# 03_Connectors.net
KiCad netlist of a schematic drawn in Altium Designer
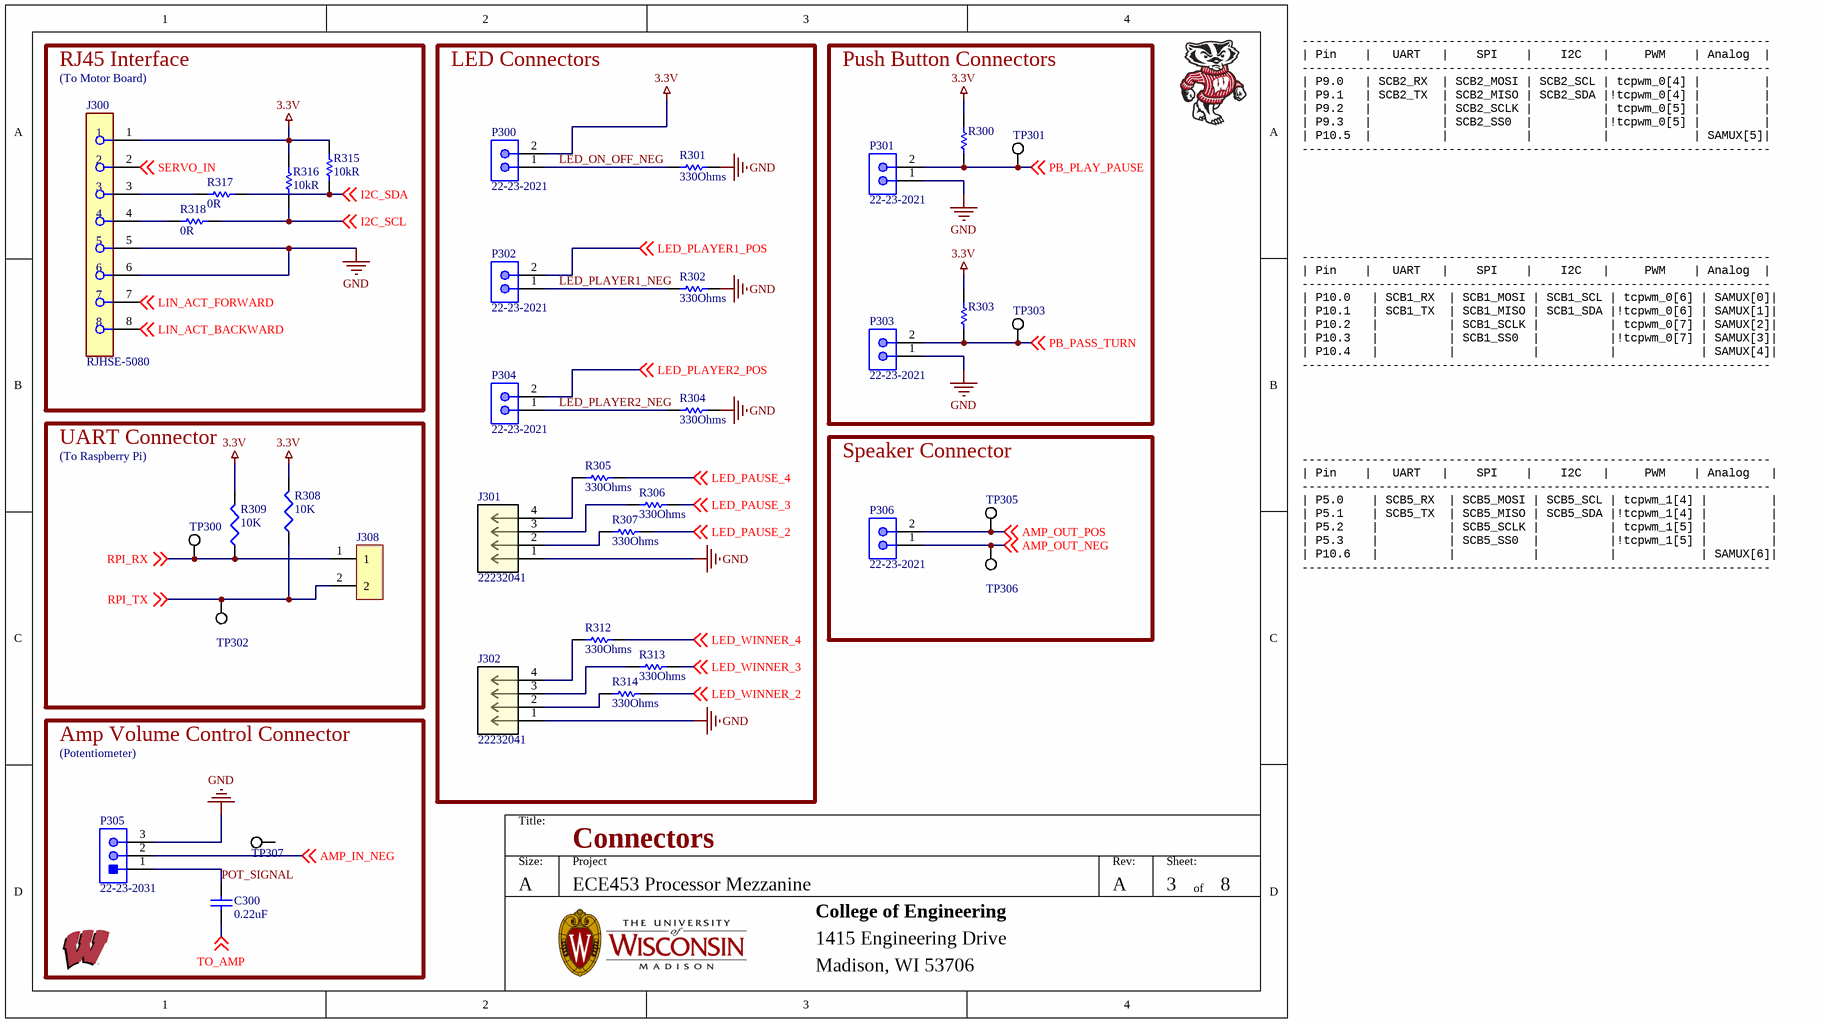
[diagram p0: 03_Connectors.SchDoc]

(export (version "E")
  (design (tool "Eeschema 10.0.6"))
  (components
    (comp (ref "C300")
      (value "0.22uF")
      (footprint "CAPC2012M")
      (description "Cap Ceramic 0.22uF 50V X7R 10% SMD 0805 125°C Plastic T/R")
      (fields
        (field (name "MANUFACTURER") "KEMET")
        (field (name "MANUFACTURER PART NUMBER") "C0805C224K5RACAUTO7210")
      )
      (libsource (lib "ECE453") (part "Cap_2"))
    )
    (comp (ref "J300")
      (value "RJHSE-5080")
      (footprint "FP-RJHSE-5080-MFG")
      (description "CONN MOD JACK 8P8C R/A UNSHLD")
      (fields
        (field (name "OCTOPART") "https://octopart.com/rjhse-5080-amphenol-45060")
        (field (name "MANUFACTURER") "Amphenol")
      )
      (libsource (lib "Altium Content Vault") (part "b0a0b555dd3abf3683e7c330df25cc4"))
    )
    (comp (ref "J301")
      (value "22232041")
      (footprint "CONN_22-23-2041_MOL")
      (description "No Description Available")
      (fields (field (name "COPYRIGHT") "Copyright (C) 2023 Ultra Librarian. All rights reserved."))
      (libsource (lib "22232041") (part "22232041"))
    )
    (comp (ref "J302")
      (value "22232041")
      (footprint "CONN_22-23-2041_MOL")
      (description "No Description Available")
      (fields (field (name "COPYRIGHT") "Copyright (C) 2023 Ultra Librarian. All rights reserved."))
      (libsource (lib "22232041") (part "22232041"))
    )
    (comp (ref "J308")
      (value "~")
      (footprint "PHOENIX2X0.2")
      (description "2~24 Poles, Screw Type, Horizontal, 5.08 Pitch, 26~14 (AWG), Terminal Block Connector")
      (fields
        (field (name "MANUFACTURER") "CUI Devices")
        (field (name "MANUFACTURER PART NUMBER") "TB006-508-02BE")
      )
      (libsource (lib "ECE453") (part "2-Pin"))
    )
    (comp (ref "P300")
      (value "22-23-2021")
      (footprint "MOLX-22-23-2021_V")
      (libsource (lib "Altium Content Vault") (part "CN-1P-M-R2"))
    )
    (comp (ref "P301")
      (value "22-23-2021")
      (footprint "MOLX-22-23-2021_V")
      (libsource (lib "Altium Content Vault") (part "CN-1P-M-R2"))
    )
    (comp (ref "P302")
      (value "22-23-2021")
      (footprint "MOLX-22-23-2021_V")
      (libsource (lib "Altium Content Vault") (part "CN-1P-M-R2"))
    )
    (comp (ref "P303")
      (value "22-23-2021")
      (footprint "MOLX-22-23-2021_V")
      (libsource (lib "Altium Content Vault") (part "CN-1P-M-R2"))
    )
    (comp (ref "P304")
      (value "22-23-2021")
      (footprint "MOLX-22-23-2021_V")
      (libsource (lib "Altium Content Vault") (part "CN-1P-M-R2"))
    )
    (comp (ref "P305")
      (value "22-23-2031")
      (footprint "MOLX-22-23-2031_V")
      (description "Male Header, Pitch 2.54 mm, 1 x 3 Position, Height 8.18 mm, Tail Length 3.56 mm, RoHS, Bulk")
      (fields (field (name "MANUFACTURER") "Molex"))
      (libsource (lib "Altium Content Vault") (part "CN-1P-M-R3"))
    )
    (comp (ref "P306")
      (value "22-23-2021")
      (footprint "MOLX-22-23-2021_V")
      (libsource (lib "Altium Content Vault") (part "CN-1P-M-R2"))
    )
    (comp (ref "R300")
      (value "RC0805FR-0710KL")
      (footprint "RESC2013X60X35NL10T20")
      (description "Chip Resistor, 10 KOhm, +/- 1%, 0.125 W, -55 to 155 degC, 0805 (2012 Metric), RoHS, Tape and Reel")
      (fields (field (name "MANUFACTURER") "Yageo"))
      (libsource (lib "Altium Content Vault") (part "RES-2"))
    )
    (comp (ref "R301")
      (value "RC0805FR-07330RL")
      (footprint "RESC2013X60X35LL10T20")
      (description "Chip Resistor, 330 Ohm, +/- 1%, 125 mW, -55 to 155 degC, 0805 (2012 Metric), RoHS, Tape and Reel")
      (fields
        (field (name "MANUFACTURER") "Yageo")
        (field (name "TOLERANCE") "1%")
        (field (name "RESISTANCE") "330Ohms")
      )
      (libsource (lib "Altium Content Vault") (part "RES-2"))
    )
    (comp (ref "R302")
      (value "RC0805FR-07330RL")
      (footprint "RESC2013X60X35LL10T20")
      (description "Chip Resistor, 330 Ohm, +/- 1%, 125 mW, -55 to 155 degC, 0805 (2012 Metric), RoHS, Tape and Reel")
      (fields
        (field (name "MANUFACTURER") "Yageo")
        (field (name "TOLERANCE") "1%")
        (field (name "RESISTANCE") "330Ohms")
      )
      (libsource (lib "Altium Content Vault") (part "RES-2"))
    )
    (comp (ref "R303")
      (value "RC0805FR-0710KL")
      (footprint "RESC2013X60X35NL10T20")
      (description "Chip Resistor, 10 KOhm, +/- 1%, 0.125 W, -55 to 155 degC, 0805 (2012 Metric), RoHS, Tape and Reel")
      (fields (field (name "MANUFACTURER") "Yageo"))
      (libsource (lib "Altium Content Vault") (part "RES-2"))
    )
    (comp (ref "R304")
      (value "RC0805FR-07330RL")
      (footprint "RESC2013X60X35LL10T20")
      (description "Chip Resistor, 330 Ohm, +/- 1%, 125 mW, -55 to 155 degC, 0805 (2012 Metric), RoHS, Tape and Reel")
      (fields
        (field (name "MANUFACTURER") "Yageo")
        (field (name "TOLERANCE") "1%")
        (field (name "RESISTANCE") "330Ohms")
      )
      (libsource (lib "Altium Content Vault") (part "RES-2"))
    )
    (comp (ref "R305")
      (value "RC0805FR-07330RL")
      (footprint "RESC2013X60X35LL10T20")
      (description "Chip Resistor, 330 Ohm, +/- 1%, 125 mW, -55 to 155 degC, 0805 (2012 Metric), RoHS, Tape and Reel")
      (fields
        (field (name "MANUFACTURER") "Yageo")
        (field (name "TOLERANCE") "1%")
        (field (name "RESISTANCE") "330Ohms")
      )
      (libsource (lib "Altium Content Vault") (part "RES-2"))
    )
    (comp (ref "R306")
      (value "RC0805FR-07330RL")
      (footprint "RESC2013X60X35LL10T20")
      (description "Chip Resistor, 330 Ohm, +/- 1%, 125 mW, -55 to 155 degC, 0805 (2012 Metric), RoHS, Tape and Reel")
      (fields
        (field (name "MANUFACTURER") "Yageo")
        (field (name "TOLERANCE") "1%")
        (field (name "RESISTANCE") "330Ohms")
      )
      (libsource (lib "Altium Content Vault") (part "RES-2"))
    )
    (comp (ref "R307")
      (value "RC0805FR-07330RL")
      (footprint "RESC2013X60X35LL10T20")
      (description "Chip Resistor, 330 Ohm, +/- 1%, 125 mW, -55 to 155 degC, 0805 (2012 Metric), RoHS, Tape and Reel")
      (fields
        (field (name "MANUFACTURER") "Yageo")
        (field (name "TOLERANCE") "1%")
        (field (name "RESISTANCE") "330Ohms")
      )
      (libsource (lib "Altium Content Vault") (part "RES-2"))
    )
    (comp (ref "R308")
      (value "10K")
      (footprint "ECE453:RESC2012M")
      (description "Res Thick Film 0805 10K Ohm 1% 0.125W ±100ppm/°C Molded SMD Paper T/R")
      (fields
        (field (name "MANUFACTURER") "Stackpole Electronics")
        (field (name "MANUFACTURER PART NUMBER") "RMCF0805FT10K0")
      )
      (libsource (lib "ECE453") (part "Res3"))
    )
    (comp (ref "R309")
      (value "10K")
      (footprint "RESC2012M")
      (description "Res Thick Film 0805 10K Ohm 1% 0.125W ±100ppm/°C Molded SMD Paper T/R")
      (fields
        (field (name "MANUFACTURER") "Stackpole Electronics")
        (field (name "MANUFACTURER PART NUMBER") "RMCF0805FT10K0")
      )
      (libsource (lib "ECE453") (part "Res3"))
    )
    (comp (ref "R312")
      (value "RC0805FR-07330RL")
      (footprint "RESC2013X60X35LL10T20")
      (description "Chip Resistor, 330 Ohm, +/- 1%, 125 mW, -55 to 155 degC, 0805 (2012 Metric), RoHS, Tape and Reel")
      (fields
        (field (name "MANUFACTURER") "Yageo")
        (field (name "TOLERANCE") "1%")
        (field (name "RESISTANCE") "330Ohms")
      )
      (libsource (lib "Altium Content Vault") (part "RES-2"))
    )
    (comp (ref "R313")
      (value "RC0805FR-07330RL")
      (footprint "RESC2013X60X35LL10T20")
      (description "Chip Resistor, 330 Ohm, +/- 1%, 125 mW, -55 to 155 degC, 0805 (2012 Metric), RoHS, Tape and Reel")
      (fields
        (field (name "MANUFACTURER") "Yageo")
        (field (name "TOLERANCE") "1%")
        (field (name "RESISTANCE") "330Ohms")
      )
      (libsource (lib "Altium Content Vault") (part "RES-2"))
    )
    (comp (ref "R314")
      (value "RC0805FR-07330RL")
      (footprint "RESC2013X60X35LL10T20")
      (description "Chip Resistor, 330 Ohm, +/- 1%, 125 mW, -55 to 155 degC, 0805 (2012 Metric), RoHS, Tape and Reel")
      (fields
        (field (name "MANUFACTURER") "Yageo")
        (field (name "TOLERANCE") "1%")
        (field (name "RESISTANCE") "330Ohms")
      )
      (libsource (lib "Altium Content Vault") (part "RES-2"))
    )
    (comp (ref "R315")
      (value "RC0805FR-0710KL")
      (footprint "RESC2013X60X35NL10T20")
      (description "Chip Resistor, 10 KOhm, +/- 1%, 0.125 W, -55 to 155 degC, 0805 (2012 Metric), RoHS, Tape and Reel")
      (fields
        (field (name "MANUFACTURER") "Yageo")
        (field (name "TOLERANCE") "1%")
        (field (name "RESISTANCE") "10kR")
      )
      (libsource (lib "ECE453") (part "CMP-1659-00013-4"))
    )
    (comp (ref "R316")
      (value "RC0805FR-0710KL")
      (footprint "RESC2013X60X35NL10T20")
      (description "Chip Resistor, 10 KOhm, +/- 1%, 0.125 W, -55 to 155 degC, 0805 (2012 Metric), RoHS, Tape and Reel")
      (fields
        (field (name "MANUFACTURER") "Yageo")
        (field (name "TOLERANCE") "1%")
        (field (name "RESISTANCE") "10kR")
      )
      (libsource (lib "ECE453") (part "CMP-1659-00013-4"))
    )
    (comp (ref "R317")
      (value "0R")
      (footprint "RESC2013X70X40NL20T20")
      (description "Chip Resistor, 0 Ohm, +/- 1%, 0.125 W, -55 to 155 degC, 0805 (2012 Metric), RoHS, Tape and Reel")
      (fields (field (name "PARTNUMBER") "ERJ-6GEY0R00V") (field (name "TOLERANCE") "5%"))
      (libsource (lib "ECE453") (part "CMP-1665-00002-5"))
    )
    (comp (ref "R318")
      (value "0R")
      (footprint "RESC2013X70X40NL20T20")
      (description "Chip Resistor, 0 Ohm, +/- 1%, 0.125 W, -55 to 155 degC, 0805 (2012 Metric), RoHS, Tape and Reel")
      (fields (field (name "PARTNUMBER") "ERJ-6GEY0R00V") (field (name "TOLERANCE") "5%"))
      (libsource (lib "ECE453") (part "CMP-1665-00002-5"))
    )
    (comp (ref "TP300")
      (value "5019")
      (footprint "KSTN-5019_V")
      (description "Test Point, 1 Position SMD, RoHS, Tape and Reel")
      (libsource (lib "Altium Content Vault") (part "TESTPOINT_WHITE"))
    )
    (comp (ref "TP301")
      (value "5019")
      (footprint "KSTN-5019_V")
      (description "Test Point, 1 Position SMD, RoHS, Tape and Reel")
      (libsource (lib "Altium Content Vault") (part "TESTPOINT_WHITE"))
    )
    (comp (ref "TP302")
      (value "5019")
      (footprint "KSTN-5019_V")
      (description "Test Point, 1 Position SMD, RoHS, Tape and Reel")
      (libsource (lib "Altium Content Vault") (part "TESTPOINT_WHITE"))
    )
    (comp (ref "TP303")
      (value "5019")
      (footprint "KSTN-5019_V")
      (description "Test Point, 1 Position SMD, RoHS, Tape and Reel")
      (libsource (lib "Altium Content Vault") (part "TESTPOINT_WHITE"))
    )
    (comp (ref "TP305")
      (value "5019")
      (footprint "KSTN-5019_V")
      (description "Test Point, 1 Position SMD, RoHS, Tape and Reel")
      (libsource (lib "Altium Content Vault") (part "TESTPOINT_WHITE"))
    )
    (comp (ref "TP306")
      (value "5019")
      (footprint "KSTN-5019_V")
      (description "Test Point, 1 Position SMD, RoHS, Tape and Reel")
      (libsource (lib "Altium Content Vault") (part "TESTPOINT_WHITE"))
    )
    (comp (ref "TP307")
      (value "5019")
      (footprint "KSTN-5019_V")
      (description "Test Point, 1 Position SMD, RoHS, Tape and Reel")
      (libsource (lib "Altium Content Vault") (part "TESTPOINT_WHITE"))
    )
  )
  (nets
    (net (code "1") (name "/LED_ON_OFF_NEG") (class "Default")
      (node (ref "P300") (pin "1") (pinfunction "1_1") (pintype "passive"))
      (node (ref "R301") (pin "2") (pinfunction "2_2") (pintype "passive"))
    )
    (net (code "2") (name "/LED_PLAYER1_NEG") (class "Default")
      (node (ref "P302") (pin "1") (pinfunction "1_1") (pintype "passive"))
      (node (ref "R302") (pin "2") (pinfunction "2_2") (pintype "passive"))
    )
    (net (code "3") (name "/LED_PLAYER2_NEG") (class "Default")
      (node (ref "P304") (pin "1") (pinfunction "1_1") (pintype "passive"))
      (node (ref "R304") (pin "2") (pinfunction "2_2") (pintype "passive"))
    )
    (net (code "4") (name "/POT_SIGNAL") (class "Default")
      (node (ref "C300") (pin "1") (pinfunction "1_1") (pintype "passive"))
      (node (ref "P305") (pin "1") (pinfunction "1_1") (pintype "passive"))
    )
    (net (code "5") (name "3.3V") (class "Default")
      (node (ref "J300") (pin "1") (pinfunction "1_1") (pintype "passive"))
      (node (ref "P300") (pin "2") (pinfunction "2_2") (pintype "passive"))
      (node (ref "R300") (pin "2") (pinfunction "2_2") (pintype "passive"))
      (node (ref "R303") (pin "2") (pinfunction "2_2") (pintype "passive"))
      (node (ref "R308") (pin "2") (pinfunction "2_2") (pintype "passive"))
      (node (ref "R309") (pin "2") (pinfunction "2_2") (pintype "passive"))
      (node (ref "R315") (pin "2") (pinfunction "2_2") (pintype "passive"))
      (node (ref "R316") (pin "2") (pinfunction "2_2") (pintype "passive"))
    )
    (net (code "6") (name "AMP_IN_NEG") (class "Default")
      (node (ref "P305") (pin "2") (pinfunction "2_2") (pintype "passive"))
    )
    (net (code "7") (name "AMP_OUT_NEG") (class "Default")
      (node (ref "P306") (pin "1") (pinfunction "1_1") (pintype "passive"))
      (node (ref "TP306") (pin "1") (pinfunction "1_1") (pintype "passive"))
    )
    (net (code "8") (name "AMP_OUT_POS") (class "Default")
      (node (ref "P306") (pin "2") (pinfunction "2_2") (pintype "passive"))
      (node (ref "TP305") (pin "1") (pinfunction "1_1") (pintype "passive"))
    )
    (net (code "9") (name "GND") (class "Default")
      (node (ref "J300") (pin "5") (pinfunction "5_5") (pintype "passive"))
      (node (ref "J300") (pin "6") (pinfunction "6_6") (pintype "passive"))
      (node (ref "J301") (pin "1") (pinfunction "1_1") (pintype "passive"))
      (node (ref "J302") (pin "1") (pinfunction "1_1") (pintype "passive"))
      (node (ref "P301") (pin "1") (pinfunction "1_1") (pintype "passive"))
      (node (ref "P303") (pin "1") (pinfunction "1_1") (pintype "passive"))
      (node (ref "P305") (pin "3") (pinfunction "3_3") (pintype "passive"))
      (node (ref "R301") (pin "1") (pinfunction "1_1") (pintype "passive"))
      (node (ref "R302") (pin "1") (pinfunction "1_1") (pintype "passive"))
      (node (ref "R304") (pin "1") (pinfunction "1_1") (pintype "passive"))
    )
    (net (code "10") (name "I2C_SCL") (class "Default")
      (node (ref "R316") (pin "1") (pinfunction "1_1") (pintype "passive"))
      (node (ref "R318") (pin "2") (pinfunction "2_2") (pintype "passive"))
    )
    (net (code "11") (name "I2C_SDA") (class "Default")
      (node (ref "R315") (pin "1") (pinfunction "1_1") (pintype "passive"))
      (node (ref "R317") (pin "2") (pinfunction "2_2") (pintype "passive"))
    )
    (net (code "12") (name "LED_PAUSE_2") (class "Default")
      (node (ref "R307") (pin "1") (pinfunction "1_1") (pintype "passive"))
    )
    (net (code "13") (name "LED_PAUSE_3") (class "Default")
      (node (ref "R306") (pin "1") (pinfunction "1_1") (pintype "passive"))
    )
    (net (code "14") (name "LED_PAUSE_4") (class "Default")
      (node (ref "R305") (pin "1") (pinfunction "1_1") (pintype "passive"))
    )
    (net (code "15") (name "LED_PLAYER1_POS") (class "Default")
      (node (ref "P302") (pin "2") (pinfunction "2_2") (pintype "passive"))
    )
    (net (code "16") (name "LED_PLAYER2_POS") (class "Default")
      (node (ref "P304") (pin "2") (pinfunction "2_2") (pintype "passive"))
    )
    (net (code "17") (name "LED_WINNER_2") (class "Default")
      (node (ref "R314") (pin "1") (pinfunction "1_1") (pintype "passive"))
    )
    (net (code "18") (name "LED_WINNER_3") (class "Default")
      (node (ref "R313") (pin "1") (pinfunction "1_1") (pintype "passive"))
    )
    (net (code "19") (name "LED_WINNER_4") (class "Default")
      (node (ref "R312") (pin "1") (pinfunction "1_1") (pintype "passive"))
    )
    (net (code "20") (name "LIN_ACT_BACKWARD") (class "Default")
      (node (ref "J300") (pin "8") (pinfunction "8_8") (pintype "passive"))
    )
    (net (code "21") (name "LIN_ACT_FORWARD") (class "Default")
      (node (ref "J300") (pin "7") (pinfunction "7_7") (pintype "passive"))
    )
    (net (code "22") (name "Net-(J300-Pad3)") (class "Default")
      (node (ref "J300") (pin "3") (pinfunction "3_3") (pintype "passive"))
      (node (ref "R317") (pin "1") (pinfunction "1_1") (pintype "passive"))
    )
    (net (code "23") (name "Net-(J300-Pad4)") (class "Default")
      (node (ref "J300") (pin "4") (pinfunction "4_4") (pintype "passive"))
      (node (ref "R318") (pin "1") (pinfunction "1_1") (pintype "passive"))
    )
    (net (code "24") (name "Net-(J301-Pad2)") (class "Default")
      (node (ref "J301") (pin "2") (pinfunction "2_2") (pintype "passive"))
      (node (ref "R307") (pin "2") (pinfunction "2_2") (pintype "passive"))
    )
    (net (code "25") (name "Net-(J301-Pad3)") (class "Default")
      (node (ref "J301") (pin "3") (pinfunction "3_3") (pintype "passive"))
      (node (ref "R306") (pin "2") (pinfunction "2_2") (pintype "passive"))
    )
    (net (code "26") (name "Net-(J301-Pad4)") (class "Default")
      (node (ref "J301") (pin "4") (pinfunction "4_4") (pintype "passive"))
      (node (ref "R305") (pin "2") (pinfunction "2_2") (pintype "passive"))
    )
    (net (code "27") (name "Net-(J302-Pad2)") (class "Default")
      (node (ref "J302") (pin "2") (pinfunction "2_2") (pintype "passive"))
      (node (ref "R314") (pin "2") (pinfunction "2_2") (pintype "passive"))
    )
    (net (code "28") (name "Net-(J302-Pad3)") (class "Default")
      (node (ref "J302") (pin "3") (pinfunction "3_3") (pintype "passive"))
      (node (ref "R313") (pin "2") (pinfunction "2_2") (pintype "passive"))
    )
    (net (code "29") (name "Net-(J302-Pad4)") (class "Default")
      (node (ref "J302") (pin "4") (pinfunction "4_4") (pintype "passive"))
      (node (ref "R312") (pin "2") (pinfunction "2_2") (pintype "passive"))
    )
    (net (code "30") (name "PB_PASS_TURN") (class "Default")
      (node (ref "P303") (pin "2") (pinfunction "2_2") (pintype "passive"))
      (node (ref "R303") (pin "1") (pinfunction "1_1") (pintype "passive"))
      (node (ref "TP303") (pin "1") (pinfunction "1_1") (pintype "passive"))
    )
    (net (code "31") (name "PB_PLAY_PAUSE") (class "Default")
      (node (ref "P301") (pin "2") (pinfunction "2_2") (pintype "passive"))
      (node (ref "R300") (pin "1") (pinfunction "1_1") (pintype "passive"))
      (node (ref "TP301") (pin "1") (pinfunction "1_1") (pintype "passive"))
    )
    (net (code "32") (name "RPI_RX") (class "Default")
      (node (ref "J308") (pin "1") (pinfunction "1_1") (pintype "passive"))
      (node (ref "R309") (pin "1") (pinfunction "1_1") (pintype "passive"))
      (node (ref "TP300") (pin "1") (pinfunction "1_1") (pintype "passive"))
    )
    (net (code "33") (name "RPI_TX") (class "Default")
      (node (ref "J308") (pin "2") (pinfunction "2_2") (pintype "passive"))
      (node (ref "R308") (pin "1") (pinfunction "1_1") (pintype "passive"))
      (node (ref "TP302") (pin "1") (pinfunction "1_1") (pintype "passive"))
    )
    (net (code "34") (name "SERVO_IN") (class "Default")
      (node (ref "J300") (pin "2") (pinfunction "2_2") (pintype "passive"))
    )
    (net (code "35") (name "TO_AMP") (class "Default")
      (node (ref "C300") (pin "2") (pinfunction "2_2") (pintype "passive"))
    )
    (net (code "36") (name "unconnected-(TP307-Pad1)") (class "Default")
      (node (ref "TP307") (pin "1") (pinfunction "1_1") (pintype "passive"))
    )
  )
)
